# 02__RF_Power.net
KiCad netlist of a schematic drawn in Altium Designer
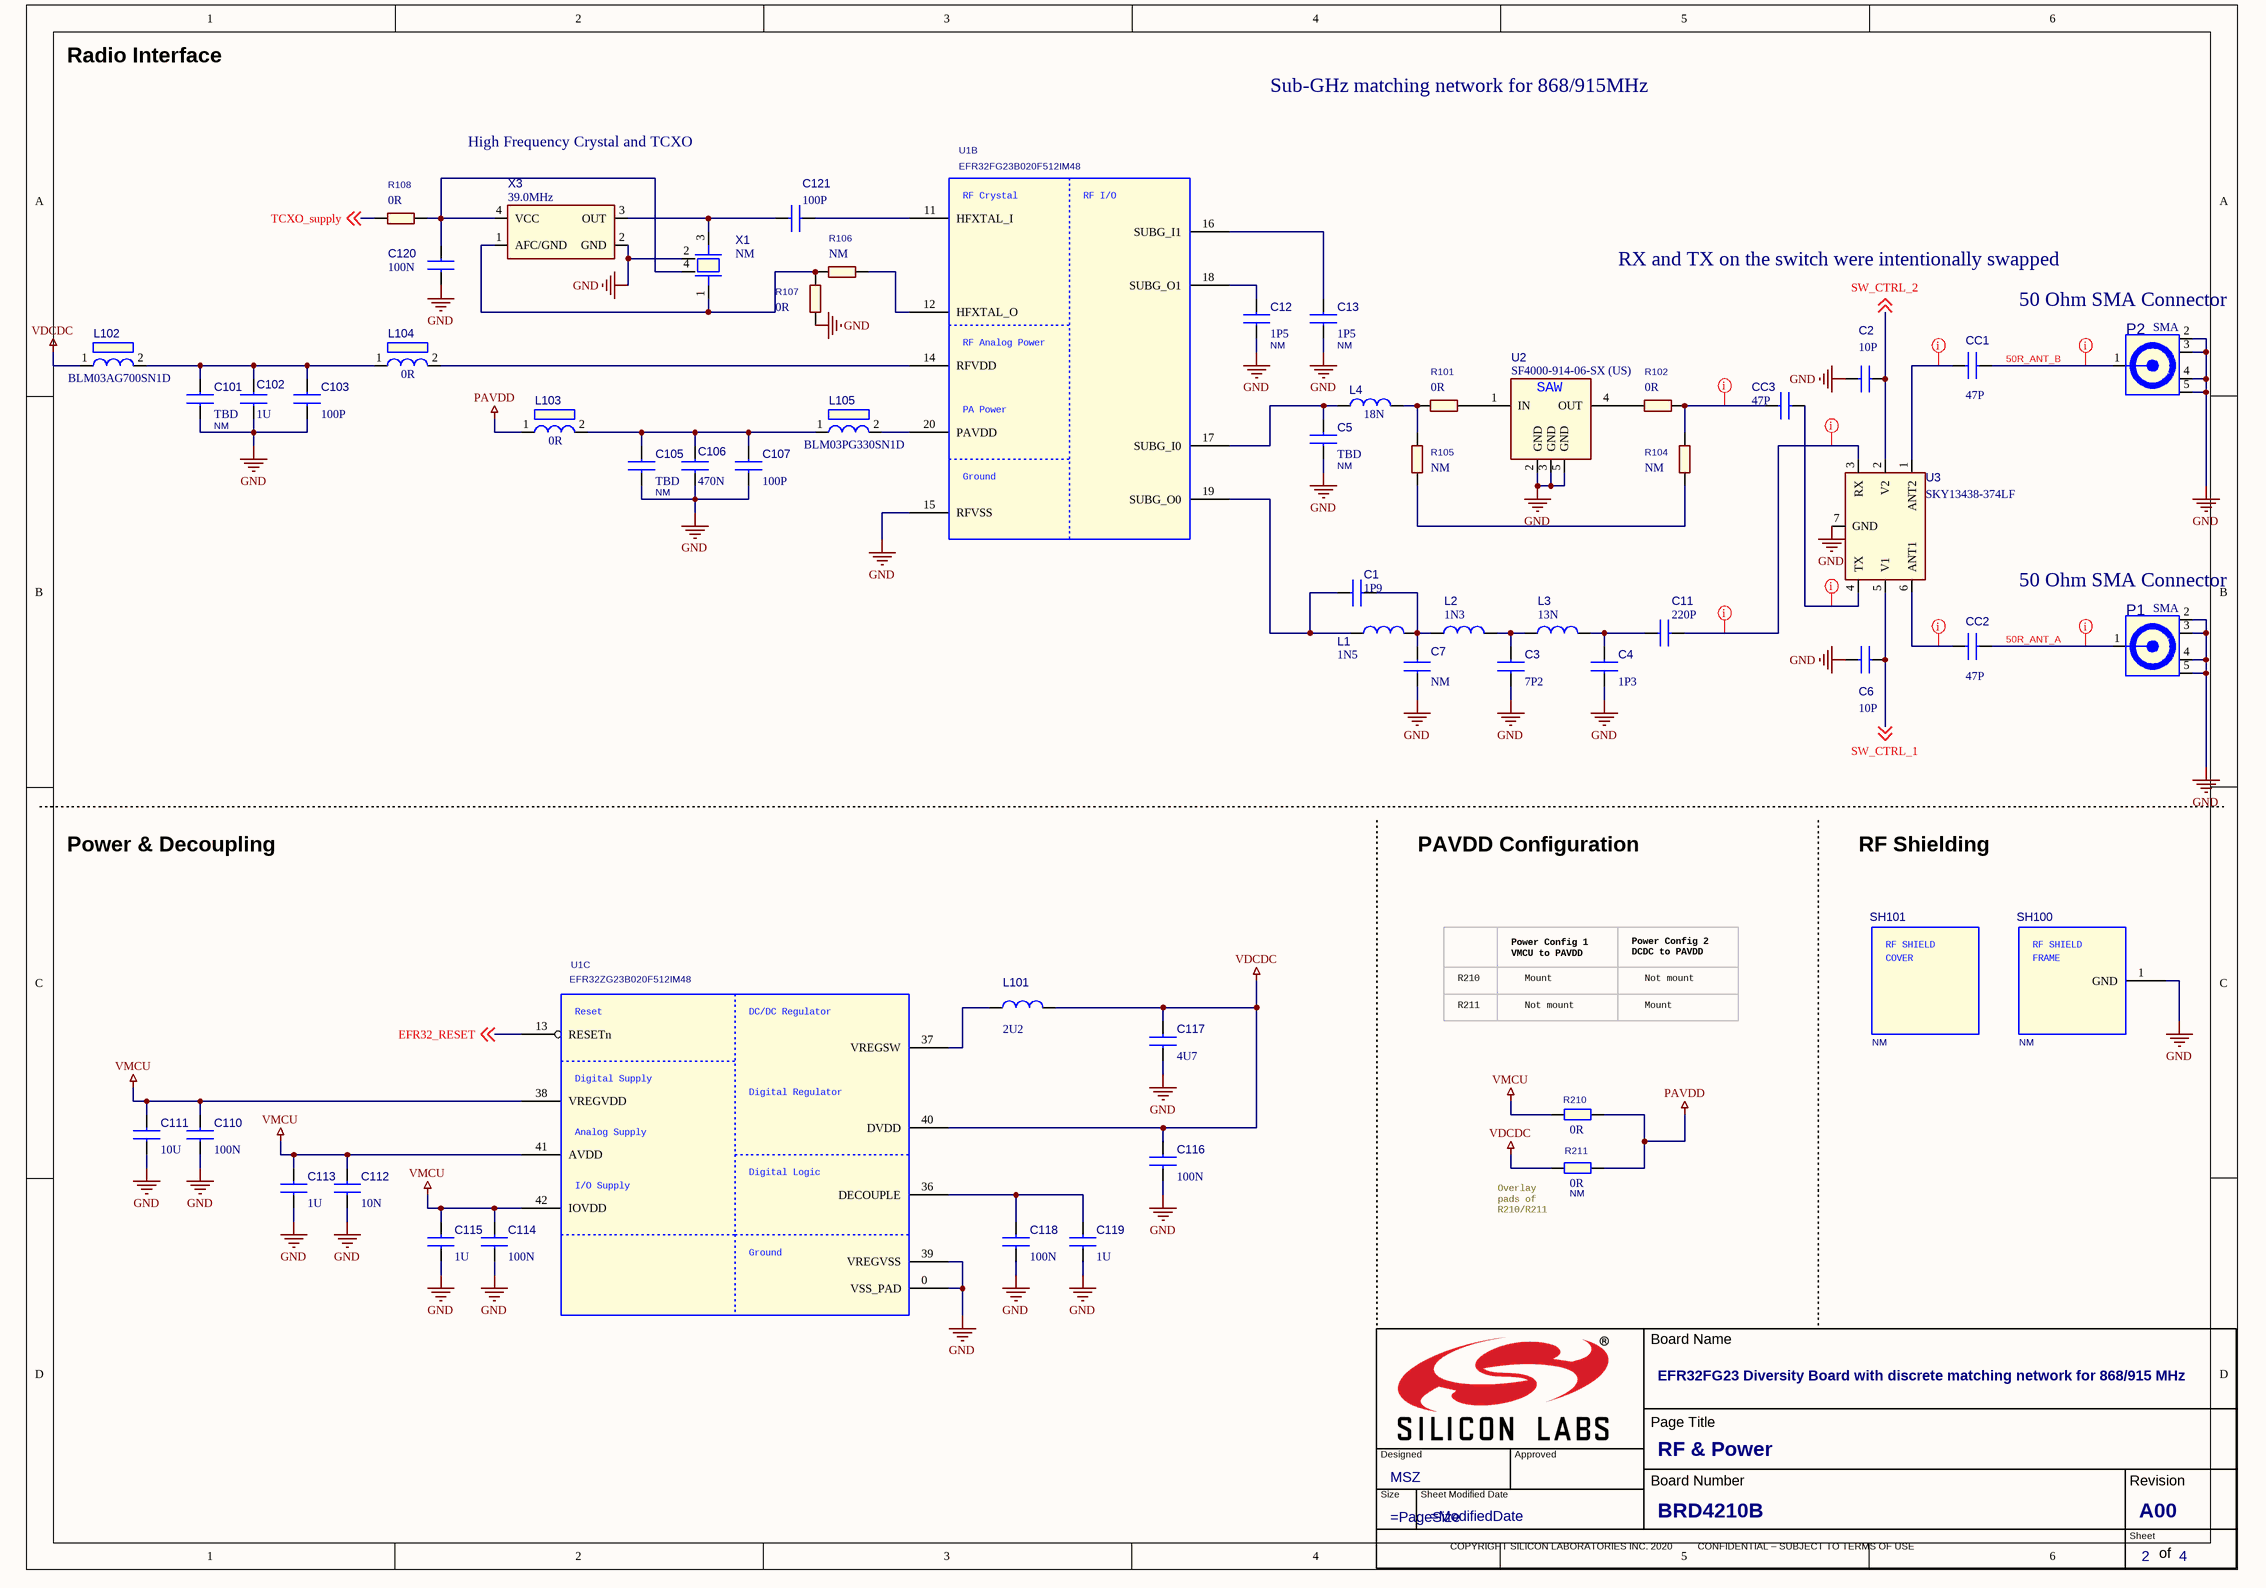
[diagram p0: 02_ RF & Power.SchDoc]

(export (version "E")
  (design (tool "Eeschema 10.0.6"))
  (components
    (comp (ref "C1")
      (value "1P9")
      (footprint "C0201_L")
      (fields (field (name "MFG") "Murata") (field (name "TOLERANCE") "±0.1pF"))
      (libsource (lib "*") (part "C0201"))
    )
    (comp (ref "C2")
      (value "10P")
      (footprint "C0201_L")
      (fields (field (name "TOLERANCE") "±2%") (field (name "MFG") "Murata"))
      (libsource (lib "*") (part "C0201"))
    )
    (comp (ref "C3")
      (value "7P2")
      (footprint "C0201_L")
      (fields (field (name "MFG") "Murata") (field (name "TOLERANCE") "±0.1pF"))
      (libsource (lib "*") (part "C0201"))
    )
    (comp (ref "C4")
      (value "1P3")
      (footprint "C0201_L")
      (fields (field (name "MFG") "Murata") (field (name "TOLERANCE") "±0.1pF"))
      (libsource (lib "*") (part "C0201"))
    )
    (comp (ref "C5")
      (value "TBD")
      (footprint "C0201_L")
      (fields (field (name "NOT MOUNTED") "NM") (field (name "TOLERANCE") "±0.05pF"))
      (libsource (lib "*") (part "C0201"))
    )
    (comp (ref "C6")
      (value "10P")
      (footprint "C0201_L")
      (fields (field (name "TOLERANCE") "±2%") (field (name "MFG") "Murata"))
      (libsource (lib "*") (part "C0201"))
    )
    (comp (ref "C7")
      (value "NM")
      (footprint "C0201_L")
      (fields (field (name "MFG") "Murata") (field (name "TOLERANCE") "±0.1pF"))
      (libsource (lib "*") (part "C0201"))
    )
    (comp (ref "C11")
      (value "220P")
      (footprint "C0201_L")
      (fields (field (name "MFG") "Murata") (field (name "TOLERANCE") "±2%"))
      (libsource (lib "*") (part "C0201"))
    )
    (comp (ref "C12")
      (value "1P5")
      (footprint "C0201_L")
      (fields
        (field (name "MFG") "Murata")
        (field (name "NOT MOUNTED") "NM")
        (field (name "TOLERANCE") "±0.05pF")
      )
      (libsource (lib "*") (part "C0201"))
    )
    (comp (ref "C13")
      (value "1P5")
      (footprint "C0201_L")
      (fields
        (field (name "MFG") "Murata")
        (field (name "NOT MOUNTED") "NM")
        (field (name "TOLERANCE") "±0.05pF")
      )
      (libsource (lib "*") (part "C0201"))
    )
    (comp (ref "C101")
      (value "TBD")
      (footprint "C0201_L")
      (fields (field (name "NOT MOUNTED") "NM") (field (name "TOLERANCE") "±0.05P"))
      (libsource (lib "*") (part "C0201"))
    )
    (comp (ref "C102")
      (value "1U")
      (footprint "C0402_L")
      (fields (field (name "TOLERANCE") "10%"))
      (libsource (lib "*") (part "C0402"))
    )
    (comp (ref "C103")
      (value "100P")
      (footprint "C0201_L")
      (fields (field (name "TOLERANCE") "5%"))
      (libsource (lib "*") (part "C0201"))
    )
    (comp (ref "C105")
      (value "TBD")
      (footprint "C0201_L")
      (fields (field (name "NOT MOUNTED") "NM") (field (name "TOLERANCE") "±0.05P"))
      (libsource (lib "*") (part "C0201"))
    )
    (comp (ref "C106")
      (value "470N")
      (footprint "C0402_L")
      (fields (field (name "TOLERANCE") "10%"))
      (libsource (lib "*") (part "C0402"))
    )
    (comp (ref "C107")
      (value "100P")
      (footprint "C0201_L")
      (fields (field (name "TOLERANCE") "5%"))
      (libsource (lib "*") (part "C0201"))
    )
    (comp (ref "C110")
      (value "100N")
      (footprint "C0201_L")
      (fields (field (name "TOLERANCE") "20%"))
      (libsource (lib "*") (part "C0201"))
    )
    (comp (ref "C111")
      (value "10U")
      (footprint "C0603_L")
      (fields (field (name "TOLERANCE") "10%"))
      (libsource (lib "*") (part "C0603"))
    )
    (comp (ref "C112")
      (value "10N")
      (footprint "C0201_L")
      (fields (field (name "TOLERANCE") "10%"))
      (libsource (lib "*") (part "C0201"))
    )
    (comp (ref "C113")
      (value "1U")
      (footprint "C0402_L")
      (fields (field (name "TOLERANCE") "10%"))
      (libsource (lib "*") (part "C0402"))
    )
    (comp (ref "C114")
      (value "100N")
      (footprint "C0201_L")
      (fields (field (name "TOLERANCE") "20%"))
      (libsource (lib "*") (part "C0201"))
    )
    (comp (ref "C115")
      (value "1U")
      (footprint "C0402_L")
      (fields (field (name "TOLERANCE") "10%"))
      (libsource (lib "*") (part "C0402"))
    )
    (comp (ref "C116")
      (value "100N")
      (footprint "C0201_L")
      (fields (field (name "TOLERANCE") "20%"))
      (libsource (lib "*") (part "C0201"))
    )
    (comp (ref "C117")
      (value "4U7")
      (footprint "C0603_L")
      (fields (field (name "TOLERANCE") "10%"))
      (libsource (lib "*") (part "C0603"))
    )
    (comp (ref "C118")
      (value "100N")
      (footprint "C0201_L")
      (fields (field (name "TOLERANCE") "20%"))
      (libsource (lib "*") (part "C0201"))
    )
    (comp (ref "C119")
      (value "1U")
      (footprint "C0402_L")
      (fields (field (name "TOLERANCE") "10%"))
      (libsource (lib "*") (part "C0402"))
    )
    (comp (ref "C120")
      (value "100N")
      (footprint "C0201_L")
      (fields (field (name "MFG") "Murata") (field (name "TOLERANCE") "±0.05pF"))
      (libsource (lib "*") (part "C0201"))
    )
    (comp (ref "C121")
      (value "100P")
      (footprint "C0201_L")
      (fields (field (name "MFG") "Murata") (field (name "TOLERANCE") "±0.05pF"))
      (libsource (lib "*") (part "C0201"))
    )
    (comp (ref "CC1")
      (value "47P")
      (footprint "C0201_L")
      (fields (field (name "TOLERANCE") "±2%") (field (name "MFG") "Murata"))
      (libsource (lib "*") (part "C0201"))
    )
    (comp (ref "CC2")
      (value "47P")
      (footprint "C0201_L")
      (fields (field (name "TOLERANCE") "±2%") (field (name "MFG") "Murata"))
      (libsource (lib "*") (part "C0201"))
    )
    (comp (ref "CC3")
      (value "47P")
      (footprint "C0201_L")
      (fields (field (name "TOLERANCE") "±2%") (field (name "MFG") "Murata"))
      (libsource (lib "*") (part "C0201"))
    )
    (comp (ref "L1")
      (value "1N5")
      (footprint "COIL_0201_L")
      (fields (field (name "MFG") "Murata") (field (name "TOLERANCE") "±0.05nH"))
      (libsource (lib "*") (part "L0201"))
    )
    (comp (ref "L2")
      (value "1N3")
      (footprint "COIL_0201_L")
      (fields (field (name "MFG") "Murata") (field (name "TOLERANCE") "±0.05nH"))
      (libsource (lib "*") (part "L0201"))
    )
    (comp (ref "L3")
      (value "13N")
      (footprint "COIL_0201_L")
      (fields (field (name "MFG") "Murata") (field (name "TOLERANCE") "±3%"))
      (libsource (lib "*") (part "L0201"))
    )
    (comp (ref "L4")
      (value "18N")
      (footprint "COIL_0201_L")
      (fields (field (name "MFG") "Murata") (field (name "TOLERANCE") "±3%"))
      (libsource (lib "*") (part "L0201"))
    )
    (comp (ref "L101")
      (value "2U2")
      (footprint "COIL_1008_L")
      (fields (field (name "TOLERANCE") "+/-20%") (field (name "MFG") "Murata"))
      (libsource (lib "*") (part "L1008"))
    )
    (comp (ref "L102")
      (value "BLM03AG700SN1D")
      (footprint "COIL_MUR_BLM03_0201")
      (fields (field (name "MFG") "Murata"))
      (libsource (lib "*") (part "BLM03AX"))
    )
    (comp (ref "L103") (value "0R") (footprint "COIL_MUR_BLM03_0201") (libsource (lib "*") (part "BLM03AX")))
    (comp (ref "L104") (value "0R") (footprint "COIL_MUR_BLM03_0201") (libsource (lib "*") (part "BLM03AX")))
    (comp (ref "L105")
      (value "BLM03PG330SN1D")
      (footprint "COIL_MUR_BLM03_0201")
      (fields (field (name "MFG") "Murata"))
      (libsource (lib "*") (part "BLM03AX"))
    )
    (comp (ref "P1")
      (value "SMA")
      (footprint "TE_SMA_1814832_TH_VER")
      (fields (field (name "MFG") "Wellshow"))
      (libsource (lib "*") (part "SMA_TH_WELLSHOW"))
    )
    (comp (ref "P2")
      (value "SMA")
      (footprint "TE_SMA_1814832_TH_VER")
      (fields (field (name "MFG") "Wellshow"))
      (libsource (lib "*") (part "SMA_TH_WELLSHOW"))
    )
    (comp (ref "R101") (value "0R") (footprint "R0201_L") (libsource (lib "BRD4210A_Library") (part "R0201")))
    (comp (ref "R102") (value "0R") (footprint "R0201_L") (libsource (lib "BRD4210A_Library") (part "R0201")))
    (comp (ref "R104") (value "NM") (footprint "R0201_L") (libsource (lib "") (part "R0201_1")))
    (comp (ref "R105") (value "NM") (footprint "R0201_L") (libsource (lib "") (part "R0201_1")))
    (comp (ref "R106") (value "NM") (footprint "R0201_L") (libsource (lib "BRD4210A_Library") (part "R0201")))
    (comp (ref "R107") (value "0R") (footprint "R0201_L") (libsource (lib "") (part "R0201_1")))
    (comp (ref "R108") (value "0R") (footprint "R0201_L") (libsource (lib "BRD4210A_Library") (part "R0201")))
    (comp (ref "R210") (value "0R") (footprint "R0402_L") (libsource (lib "*") (part "R0402")))
    (comp (ref "R211")
      (value "0R")
      (footprint "R0402_L")
      (fields (field (name "NOT MOUNTED") "NM"))
      (libsource (lib "") (part "R0402_1"))
    )
    (comp (ref "SH100")
      (value "RF_SHIELD_FRAME_36103205S")
      (footprint "Shield_21x21mm")
      (fields (field (name "NOT MOUNTED") "NM") (field (name "MFG") "Würth Elektronik"))
      (libsource (lib "*") (part "RF_SHIELD_FRAME_36103205S"))
    )
    (comp (ref "SH101")
      (value "RF_SHIELD_COVER_36003200S")
      (fields (field (name "NOT MOUNTED") "NM") (field (name "MFG") "Würth Elektronik"))
      (libsource (lib "*") (part "RF_SHIELD_COVER_36003200S"))
    )
    (comp (ref "U1")
      (value "EFR32ZG23B020F512IM48")
      (footprint "QFN48_M040_6.0X6.0_EP_SL")
      (fields (field (name "MFG") "Silicon Labs"))
      (libsource (lib "*") (part "EFR32xG23_QFN48"))
    )
    (comp (ref "U2")
      (value "SF4000-914-06-SX (US)")
      (footprint "SF1256")
      (description "B2645 from Qualcomm also fits")
      (fields (field (name "MFG") "ACTE"))
      (libsource (lib "BRD4210A_Library") (part "SF4000-914-06-SX"))
    )
    (comp (ref "U3")
      (value "SKY13438-374LF")
      (footprint "SKY13438-374LF")
      (fields (field (name "MFG") "Infineon"))
      (libsource (lib "BRD4210A_Library") (part "SKY13438-374LF"))
    )
    (comp (ref "X1")
      (value "NM")
      (footprint "X_SSS_DSX211SH_2.05X1.65-4")
      (fields (field (name "MFG") "Tai-Saw"))
      (libsource (lib "*") (part "DSX211SH"))
    )
    (comp (ref "X3")
      (value "39.0MHz")
      (footprint "TCXO_7Z-38.400MBG-T_SMD2016_TXC")
      (fields (field (name "MFG") "TXC"))
      (libsource (lib "BRD4210A_Library") (part "7Z-38.400MBG-T"))
    )
  )
  (nets
    (net (code "1") (name "/50R_ANT_A") (class "Default")
      (node (ref "CC2") (pin "2") (pinfunction "2_2") (pintype "passive"))
      (node (ref "P1") (pin "1") (pinfunction "SIGNAL_1") (pintype "passive"))
    )
    (net (code "2") (name "/50R_ANT_B") (class "Default")
      (node (ref "CC1") (pin "2") (pinfunction "2_2") (pintype "passive"))
      (node (ref "P2") (pin "1") (pinfunction "SIGNAL_1") (pintype "passive"))
    )
    (net (code "3") (name "EFR32_RESET") (class "Default")
      (node (ref "U1") (pin "13") (pinfunction "RESETn_13") (pintype "passive"))
    )
    (net (code "4") (name "GND") (class "Default")
      (node (ref "C101") (pin "2") (pinfunction "2_2") (pintype "passive"))
      (node (ref "C102") (pin "2") (pinfunction "2_2") (pintype "passive"))
      (node (ref "C103") (pin "2") (pinfunction "2_2") (pintype "passive"))
      (node (ref "C105") (pin "2") (pinfunction "2_2") (pintype "passive"))
      (node (ref "C106") (pin "2") (pinfunction "2_2") (pintype "passive"))
      (node (ref "C107") (pin "2") (pinfunction "2_2") (pintype "passive"))
      (node (ref "C110") (pin "2") (pinfunction "2_2") (pintype "passive"))
      (node (ref "C111") (pin "2") (pinfunction "2_2") (pintype "passive"))
      (node (ref "C112") (pin "2") (pinfunction "2_2") (pintype "passive"))
      (node (ref "C113") (pin "2") (pinfunction "2_2") (pintype "passive"))
      (node (ref "C114") (pin "2") (pinfunction "2_2") (pintype "passive"))
      (node (ref "C115") (pin "2") (pinfunction "2_2") (pintype "passive"))
      (node (ref "C116") (pin "2") (pinfunction "2_2") (pintype "passive"))
      (node (ref "C117") (pin "2") (pinfunction "2_2") (pintype "passive"))
      (node (ref "C118") (pin "2") (pinfunction "2_2") (pintype "passive"))
      (node (ref "C119") (pin "2") (pinfunction "2_2") (pintype "passive"))
      (node (ref "C12") (pin "2") (pinfunction "2_2") (pintype "passive"))
      (node (ref "C120") (pin "2") (pinfunction "2_2") (pintype "passive"))
      (node (ref "C13") (pin "2") (pinfunction "2_2") (pintype "passive"))
      (node (ref "C2") (pin "1") (pinfunction "1_1") (pintype "passive"))
      (node (ref "C3") (pin "2") (pinfunction "2_2") (pintype "passive"))
      (node (ref "C4") (pin "2") (pinfunction "2_2") (pintype "passive"))
      (node (ref "C5") (pin "2") (pinfunction "2_2") (pintype "passive"))
      (node (ref "C6") (pin "1") (pinfunction "1_1") (pintype "passive"))
      (node (ref "C7") (pin "2") (pinfunction "2_2") (pintype "passive"))
      (node (ref "P1") (pin "2") (pinfunction "GND1_2") (pintype "passive"))
      (node (ref "P1") (pin "3") (pinfunction "GND2_3") (pintype "passive"))
      (node (ref "P1") (pin "4") (pinfunction "GND3_4") (pintype "passive"))
      (node (ref "P1") (pin "5") (pinfunction "GND4_5") (pintype "passive"))
      (node (ref "P2") (pin "2") (pinfunction "GND1_2") (pintype "passive"))
      (node (ref "P2") (pin "3") (pinfunction "GND2_3") (pintype "passive"))
      (node (ref "P2") (pin "4") (pinfunction "GND3_4") (pintype "passive"))
      (node (ref "P2") (pin "5") (pinfunction "GND4_5") (pintype "passive"))
      (node (ref "R107") (pin "2") (pinfunction "2_2") (pintype "passive"))
      (node (ref "SH100") (pin "1") (pinfunction "GND_1") (pintype "passive"))
      (node (ref "U1") (pin "0") (pinfunction "VSS_PAD_0") (pintype "power_in"))
      (node (ref "U1") (pin "15") (pinfunction "RFVSS_15") (pintype "passive"))
      (node (ref "U1") (pin "39") (pinfunction "VREGVSS_39") (pintype "passive"))
      (node (ref "U2") (pin "2") (pinfunction "GND_2") (pintype "passive"))
      (node (ref "U2") (pin "3") (pinfunction "GND_3") (pintype "passive"))
      (node (ref "U2") (pin "5") (pinfunction "GND_5") (pintype "passive"))
      (node (ref "U3") (pin "7") (pinfunction "GND_7") (pintype "passive"))
      (node (ref "X1") (pin "2") (pinfunction "2_2") (pintype "passive"))
      (node (ref "X3") (pin "2") (pinfunction "GND_2") (pintype "passive"))
    )
    (net (code "5") (name "Net-(C1-Pad2)") (class "Default")
      (node (ref "C1") (pin "2") (pinfunction "2_2") (pintype "passive"))
      (node (ref "C7") (pin "1") (pinfunction "1_1") (pintype "passive"))
      (node (ref "L1") (pin "2") (pinfunction "2_2") (pintype "passive"))
      (node (ref "L2") (pin "1") (pinfunction "1_1") (pintype "passive"))
    )
    (net (code "6") (name "Net-(C3-Pad1)") (class "Default")
      (node (ref "C3") (pin "1") (pinfunction "1_1") (pintype "passive"))
      (node (ref "L2") (pin "2") (pinfunction "2_2") (pintype "passive"))
      (node (ref "L3") (pin "1") (pinfunction "1_1") (pintype "passive"))
    )
    (net (code "7") (name "Net-(C11-Pad1)") (class "Default")
      (node (ref "C11") (pin "1") (pinfunction "1_1") (pintype "passive"))
      (node (ref "C4") (pin "1") (pinfunction "1_1") (pintype "passive"))
      (node (ref "L3") (pin "2") (pinfunction "2_2") (pintype "passive"))
    )
    (net (code "8") (name "Net-(C101-Pad1)") (class "Default")
      (node (ref "C101") (pin "1") (pinfunction "1_1") (pintype "passive"))
      (node (ref "C102") (pin "1") (pinfunction "1_1") (pintype "passive"))
      (node (ref "C103") (pin "1") (pinfunction "1_1") (pintype "passive"))
      (node (ref "L102") (pin "2") (pinfunction "2_2") (pintype "passive"))
      (node (ref "L104") (pin "1") (pinfunction "1_1") (pintype "passive"))
    )
    (net (code "9") (name "Net-(C105-Pad1)") (class "Default")
      (node (ref "C105") (pin "1") (pinfunction "1_1") (pintype "passive"))
      (node (ref "C106") (pin "1") (pinfunction "1_1") (pintype "passive"))
      (node (ref "C107") (pin "1") (pinfunction "1_1") (pintype "passive"))
      (node (ref "L103") (pin "2") (pinfunction "2_2") (pintype "passive"))
      (node (ref "L105") (pin "1") (pinfunction "1_1") (pintype "passive"))
    )
    (net (code "10") (name "Net-(CC3-Pad1)") (class "Default")
      (node (ref "CC3") (pin "1") (pinfunction "1_1") (pintype "passive"))
      (node (ref "R102") (pin "2") (pinfunction "2_2") (pintype "passive"))
      (node (ref "R104") (pin "1") (pinfunction "1_1") (pintype "passive"))
    )
    (net (code "11") (name "Net-(L4-Pad2)") (class "Default")
      (node (ref "L4") (pin "2") (pinfunction "2_2") (pintype "passive"))
      (node (ref "R101") (pin "1") (pinfunction "1_1") (pintype "passive"))
      (node (ref "R105") (pin "1") (pinfunction "1_1") (pintype "passive"))
    )
    (net (code "12") (name "Net-(R104-Pad2)") (class "Default")
      (node (ref "R104") (pin "2") (pinfunction "2_2") (pintype "passive"))
      (node (ref "R105") (pin "2") (pinfunction "2_2") (pintype "passive"))
    )
    (net (code "13") (name "Net-(U1B-HFXTAL_I)") (class "Default")
      (node (ref "C121") (pin "2") (pinfunction "2_2") (pintype "passive"))
      (node (ref "U1") (pin "11") (pinfunction "HFXTAL_I_11") (pintype "passive"))
    )
    (net (code "14") (name "Net-(U1B-HFXTAL_O)") (class "Default")
      (node (ref "R106") (pin "2") (pinfunction "2_2") (pintype "passive"))
      (node (ref "U1") (pin "12") (pinfunction "HFXTAL_O_12") (pintype "passive"))
    )
    (net (code "15") (name "Net-(U1B-PAVDD)") (class "Default")
      (node (ref "L105") (pin "2") (pinfunction "2_2") (pintype "passive"))
      (node (ref "U1") (pin "20") (pinfunction "PAVDD_20") (pintype "passive"))
    )
    (net (code "16") (name "Net-(U1B-RFVDD)") (class "Default")
      (node (ref "L104") (pin "2") (pinfunction "2_2") (pintype "passive"))
      (node (ref "U1") (pin "14") (pinfunction "RFVDD_14") (pintype "power_in"))
    )
    (net (code "17") (name "Net-(U1B-SUBG_I0)") (class "Default")
      (node (ref "C5") (pin "1") (pinfunction "1_1") (pintype "passive"))
      (node (ref "L4") (pin "1") (pinfunction "1_1") (pintype "passive"))
      (node (ref "U1") (pin "17") (pinfunction "SUBG_I0_17") (pintype "passive"))
    )
    (net (code "18") (name "Net-(U1B-SUBG_I1)") (class "Default")
      (node (ref "C13") (pin "1") (pinfunction "1_1") (pintype "passive"))
      (node (ref "U1") (pin "16") (pinfunction "SUBG_I1_16") (pintype "passive"))
    )
    (net (code "19") (name "Net-(U1B-SUBG_O0)") (class "Default")
      (node (ref "C1") (pin "1") (pinfunction "1_1") (pintype "passive"))
      (node (ref "L1") (pin "1") (pinfunction "1_1") (pintype "passive"))
      (node (ref "U1") (pin "19") (pinfunction "SUBG_O0_19") (pintype "passive"))
    )
    (net (code "20") (name "Net-(U1B-SUBG_O1)") (class "Default")
      (node (ref "C12") (pin "1") (pinfunction "1_1") (pintype "passive"))
      (node (ref "U1") (pin "18") (pinfunction "SUBG_O1_18") (pintype "passive"))
    )
    (net (code "21") (name "Net-(U1C-DECOUPLE)") (class "Default")
      (node (ref "C118") (pin "1") (pinfunction "1_1") (pintype "passive"))
      (node (ref "C119") (pin "1") (pinfunction "1_1") (pintype "passive"))
      (node (ref "U1") (pin "36") (pinfunction "DECOUPLE_36") (pintype "power_in"))
    )
    (net (code "22") (name "Net-(U1C-VREGSW)") (class "Default")
      (node (ref "L101") (pin "1") (pinfunction "1_1") (pintype "passive"))
      (node (ref "U1") (pin "37") (pinfunction "VREGSW_37") (pintype "passive"))
    )
    (net (code "23") (name "Net-(U2-IN)") (class "Default")
      (node (ref "R101") (pin "2") (pinfunction "2_2") (pintype "passive"))
      (node (ref "U2") (pin "1") (pinfunction "IN_1") (pintype "passive"))
    )
    (net (code "24") (name "Net-(U2-OUT)") (class "Default")
      (node (ref "R102") (pin "1") (pinfunction "1_1") (pintype "passive"))
      (node (ref "U2") (pin "4") (pinfunction "OUT_4") (pintype "passive"))
    )
    (net (code "25") (name "Net-(U3-ANT1)") (class "Default")
      (node (ref "CC2") (pin "1") (pinfunction "1_1") (pintype "passive"))
      (node (ref "U3") (pin "6") (pinfunction "ANT1_6") (pintype "passive"))
    )
    (net (code "26") (name "Net-(U3-ANT2)") (class "Default")
      (node (ref "CC1") (pin "1") (pinfunction "1_1") (pintype "passive"))
      (node (ref "U3") (pin "1") (pinfunction "ANT2_1") (pintype "passive"))
    )
    (net (code "27") (name "Net-(U3-RX)") (class "Default")
      (node (ref "C11") (pin "2") (pinfunction "2_2") (pintype "passive"))
      (node (ref "U3") (pin "3") (pinfunction "RX_3") (pintype "passive"))
    )
    (net (code "28") (name "Net-(U3-TX)") (class "Default")
      (node (ref "CC3") (pin "2") (pinfunction "2_2") (pintype "passive"))
      (node (ref "U3") (pin "4") (pinfunction "TX_4") (pintype "passive"))
    )
    (net (code "29") (name "Net-(X3-AFC{slash}GND)") (class "Default")
      (node (ref "R106") (pin "1") (pinfunction "1_1") (pintype "passive"))
      (node (ref "R107") (pin "1") (pinfunction "1_1") (pintype "passive"))
      (node (ref "X1") (pin "1") (pinfunction "1_1") (pintype "passive"))
      (node (ref "X3") (pin "1") (pinfunction "AFC/GND_1") (pintype "passive"))
    )
    (net (code "30") (name "Net-(X3-OUT)") (class "Default")
      (node (ref "C121") (pin "1") (pinfunction "1_1") (pintype "passive"))
      (node (ref "X1") (pin "3") (pinfunction "3_3") (pintype "passive"))
      (node (ref "X3") (pin "3") (pinfunction "OUT_3") (pintype "passive"))
    )
    (net (code "31") (name "Net-(X3-VCC)") (class "Default")
      (node (ref "C120") (pin "1") (pinfunction "1_1") (pintype "passive"))
      (node (ref "R108") (pin "2") (pinfunction "2_2") (pintype "passive"))
      (node (ref "X1") (pin "4") (pinfunction "4_4") (pintype "passive"))
      (node (ref "X3") (pin "4") (pinfunction "VCC_4") (pintype "passive"))
    )
    (net (code "32") (name "PAVDD") (class "Default")
      (node (ref "L103") (pin "1") (pinfunction "1_1") (pintype "passive"))
      (node (ref "R210") (pin "1") (pinfunction "1_1") (pintype "passive"))
      (node (ref "R211") (pin "2") (pinfunction "2_2") (pintype "passive"))
    )
    (net (code "33") (name "SW_CTRL_1") (class "Default")
      (node (ref "C6") (pin "2") (pinfunction "2_2") (pintype "passive"))
      (node (ref "U3") (pin "5") (pinfunction "V1_5") (pintype "passive"))
    )
    (net (code "34") (name "SW_CTRL_2") (class "Default")
      (node (ref "C2") (pin "2") (pinfunction "2_2") (pintype "passive"))
      (node (ref "U3") (pin "2") (pinfunction "V2_2") (pintype "passive"))
    )
    (net (code "35") (name "TCXO_supply") (class "Default")
      (node (ref "R108") (pin "1") (pinfunction "1_1") (pintype "passive"))
    )
    (net (code "36") (name "VDCDC") (class "Default")
      (node (ref "C116") (pin "1") (pinfunction "1_1") (pintype "passive"))
      (node (ref "C117") (pin "1") (pinfunction "1_1") (pintype "passive"))
      (node (ref "L101") (pin "2") (pinfunction "2_2") (pintype "passive"))
      (node (ref "L102") (pin "1") (pinfunction "1_1") (pintype "passive"))
      (node (ref "R211") (pin "1") (pinfunction "1_1") (pintype "passive"))
      (node (ref "U1") (pin "40") (pinfunction "DVDD_40") (pintype "power_in"))
    )
    (net (code "37") (name "VMCU") (class "Default")
      (node (ref "C110") (pin "1") (pinfunction "1_1") (pintype "passive"))
      (node (ref "C111") (pin "1") (pinfunction "1_1") (pintype "passive"))
      (node (ref "C112") (pin "1") (pinfunction "1_1") (pintype "passive"))
      (node (ref "C113") (pin "1") (pinfunction "1_1") (pintype "passive"))
      (node (ref "C114") (pin "1") (pinfunction "1_1") (pintype "passive"))
      (node (ref "C115") (pin "1") (pinfunction "1_1") (pintype "passive"))
      (node (ref "R210") (pin "2") (pinfunction "2_2") (pintype "passive"))
      (node (ref "U1") (pin "38") (pinfunction "VREGVDD_38") (pintype "passive"))
      (node (ref "U1") (pin "41") (pinfunction "AVDD_41") (pintype "power_in"))
      (node (ref "U1") (pin "42") (pinfunction "IOVDD_42") (pintype "power_in"))
    )
  )
)
